# Basic_Arduino_Shield.net
KiCad netlist of a schematic drawn in Altium Designer
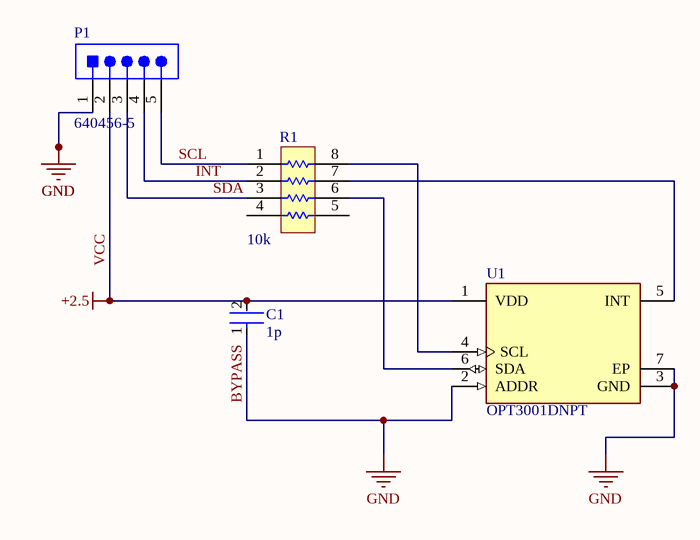
[diagram p0: Basic Arduino Shield.SchDoc]

(export (version "E")
  (design (tool "Eeschema 10.0.6"))
  (components
    (comp (ref "C1")
      (value "1p")
      (footprint "FP-C0603C-CF-MFG")
      (description "CAP CER 1PF 50V C0G/NP0 0603 straight male header")
      (fields (field (name "TOLERANCE") "0.25 pF") (field (name "MANUFACTURER") "KEMET"))
      (libsource (lib "Altium Content Vault") (part "b4654b650e69147ec39a6b967a45e02"))
    )
    (comp (ref "P1")
      (value "640456-5")
      (footprint "TECO-640456-5")
      (fields (field (name "MANUFACTURER") "TE Connectivity"))
      (libsource (lib "Altium Content Vault") (part "CN-1P-M-R5"))
    )
    (comp (ref "R1")
      (value "10k")
      (footprint "BOUR-CAT16-103J4LF_L")
      (fields (field (name "MANUFACTURER") "Bourns") (field (name "TOLERANCE") "±5%"))
      (libsource (lib "Altium Content Vault") (part "RES-P-8"))
    )
    (comp (ref "U1")
      (value "OPT3001DNPT")
      (footprint "FP-DNP0006A-IPC_C")
      (description "SENSOR OPT 550NM AMBIENT 6USON")
      (libsource (lib "Altium Content Vault") (part "55852517be4260b089306e3344175af"))
    )
  )
  (nets
    (net (code "1") (name "+2.5") (class "Default")
      (node (ref "C1") (pin "2") (pinfunction "2_2") (pintype "passive"))
      (node (ref "P1") (pin "2") (pinfunction "RXI_2") (pintype "passive"))
      (node (ref "U1") (pin "1") (pinfunction "VDD_1") (pintype "power_in"))
    )
    (net (code "2") (name "/INT") (class "Default")
      (node (ref "P1") (pin "4") (pinfunction "VCC_4") (pintype "passive"))
      (node (ref "R1") (pin "2") (pinfunction "2_2") (pintype "passive"))
    )
    (net (code "3") (name "/SCL") (class "Default")
      (node (ref "P1") (pin "5") (pinfunction "CTS_5") (pintype "passive"))
      (node (ref "R1") (pin "1") (pinfunction "1_1") (pintype "passive"))
    )
    (net (code "4") (name "/SDA") (class "Default")
      (node (ref "P1") (pin "3") (pinfunction "TXO_3") (pintype "passive"))
      (node (ref "R1") (pin "3") (pinfunction "3_3") (pintype "passive"))
    )
    (net (code "5") (name "GND") (class "Default")
      (node (ref "C1") (pin "1") (pinfunction "1_1") (pintype "passive"))
      (node (ref "P1") (pin "1") (pinfunction "DTR_1") (pintype "passive"))
      (node (ref "U1") (pin "2") (pinfunction "ADDR_2") (pintype "input"))
      (node (ref "U1") (pin "3") (pinfunction "GND_3") (pintype "power_in"))
      (node (ref "U1") (pin "7") (pinfunction "EP_7") (pintype "power_in"))
    )
    (net (code "6") (name "Net-(U1-INT)") (class "Default")
      (node (ref "R1") (pin "7") (pinfunction "7_7") (pintype "passive"))
      (node (ref "U1") (pin "5") (pinfunction "INT_5") (pintype "open_collector"))
    )
    (net (code "7") (name "Net-(U1-SCL)") (class "Default")
      (node (ref "R1") (pin "8") (pinfunction "8_8") (pintype "passive"))
      (node (ref "U1") (pin "4") (pinfunction "SCL_4") (pintype "input"))
    )
    (net (code "8") (name "Net-(U1-SDA)") (class "Default")
      (node (ref "R1") (pin "6") (pinfunction "6_6") (pintype "passive"))
      (node (ref "U1") (pin "6") (pinfunction "SDA_6") (pintype "bidirectional"))
    )
    (net (code "9") (name "unconnected-(R1-Pad4)") (class "Default")
      (node (ref "R1") (pin "4") (pinfunction "4_4") (pintype "passive"))
    )
    (net (code "10") (name "unconnected-(R1-Pad5)") (class "Default")
      (node (ref "R1") (pin "5") (pinfunction "5_5") (pintype "passive"))
    )
  )
)
